# Bank2_Configuration.net
KiCad netlist of a schematic drawn in Altium Designer
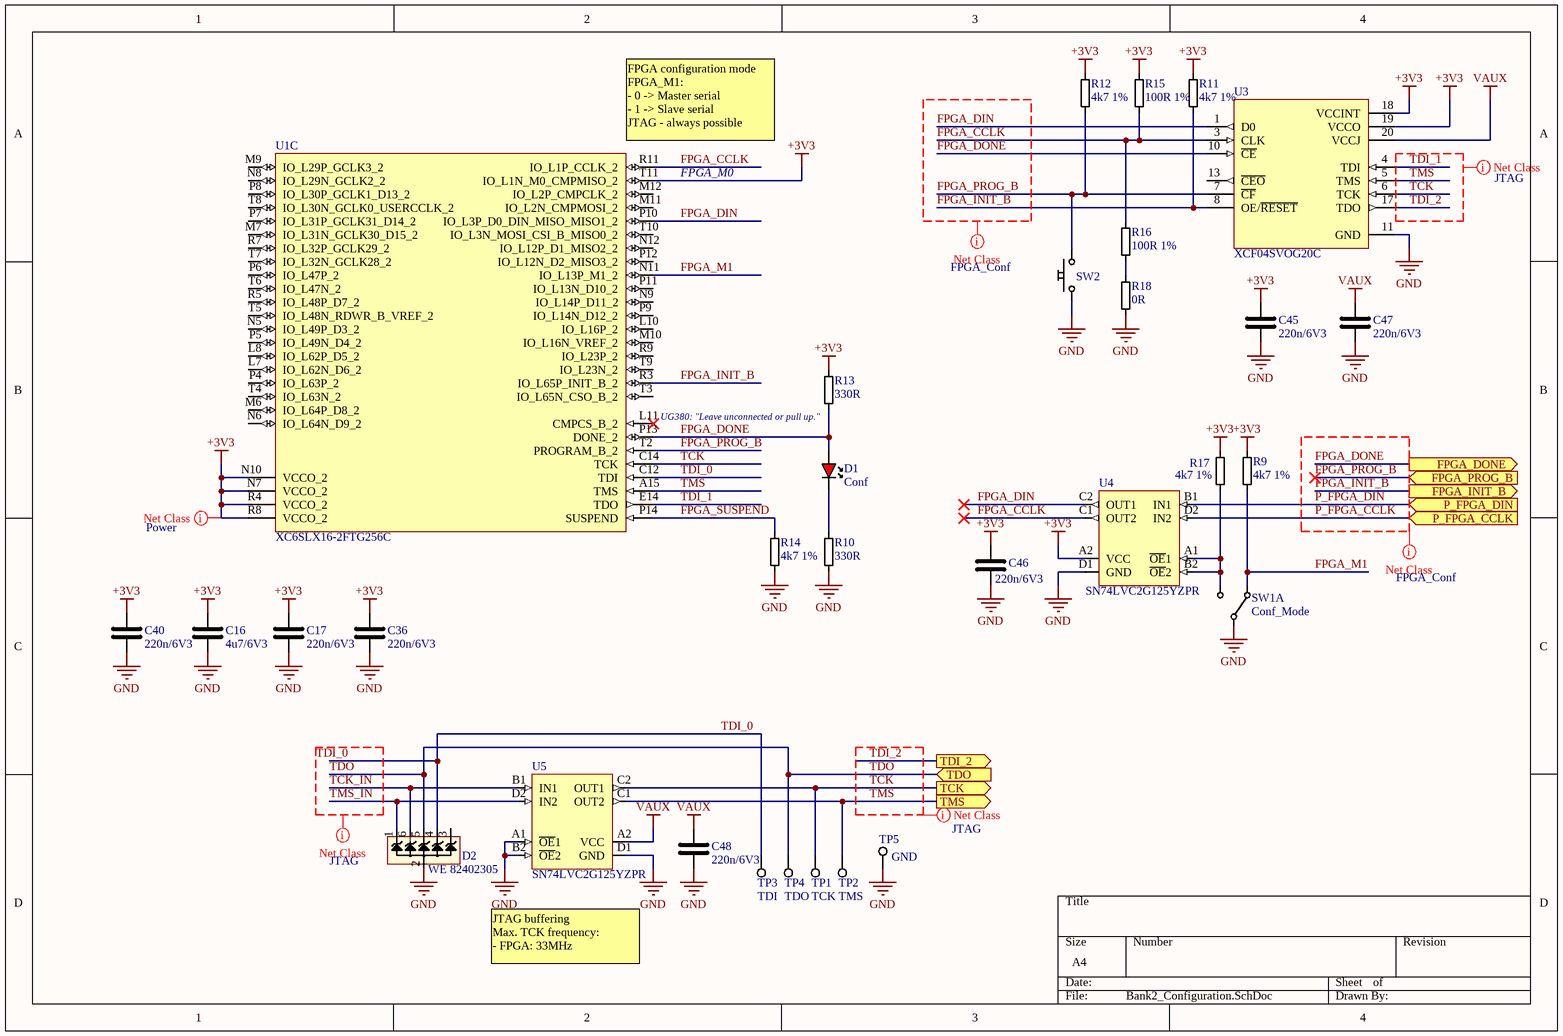
[diagram p0: Bank2_Configuration.SchDoc]

(export (version "E")
  (design (tool "Eeschema 10.0.6"))
  (components
    (comp (ref "C16") (value "4u7/6V3") (footprint "C0805_N") (libsource (lib "niceCircuits") (part "C")))
    (comp (ref "C17") (value "220n/6V3") (footprint "C0402_N") (libsource (lib "niceCircuits") (part "C")))
    (comp (ref "C36") (value "220n/6V3") (footprint "C0402_N") (libsource (lib "niceCircuits") (part "C")))
    (comp (ref "C40") (value "220n/6V3") (footprint "C0402_N") (libsource (lib "niceCircuits") (part "C")))
    (comp (ref "C45") (value "220n/6V3") (footprint "C0402_N") (libsource (lib "niceCircuits") (part "C")))
    (comp (ref "C46") (value "220n/6V3") (footprint "C0402_N") (libsource (lib "niceCircuits") (part "C")))
    (comp (ref "C47") (value "220n/6V3") (footprint "C0402_N") (libsource (lib "niceCircuits") (part "C")))
    (comp (ref "C48") (value "220n/6V3") (footprint "C0402_N") (libsource (lib "niceCircuits") (part "C")))
    (comp (ref "D1")
      (value "Conf")
      (footprint "LED0603_red_N")
      (description "Generic 0603 Super Bright Red LED")
      (libsource (lib "niceCircuits") (part "LED_0603_Red_Super_Bright"))
    )
    (comp (ref "D2")
      (value "WE 82402305")
      (footprint "SOT23-6_N")
      (description "TVS Diode WE-TVS-Standard, VRWM=5.0V")
      (libsource (lib "niceCircuits") (part "WE 82402305"))
    )
    (comp (ref "R9") (value "4k7 1%") (footprint "R0402_N") (libsource (lib "niceCircuits") (part "R")))
    (comp (ref "R10") (value "330R") (footprint "R0402_N") (libsource (lib "niceCircuits") (part "R")))
    (comp (ref "R11") (value "4k7 1%") (footprint "R0402_N") (libsource (lib "niceCircuits") (part "R")))
    (comp (ref "R12") (value "4k7 1%") (footprint "R0402_N") (libsource (lib "niceCircuits") (part "R")))
    (comp (ref "R13") (value "330R") (footprint "R0402_N") (libsource (lib "niceCircuits") (part "R")))
    (comp (ref "R14") (value "4k7 1%") (footprint "R0402_N") (libsource (lib "niceCircuits") (part "R")))
    (comp (ref "R15") (value "100R 1%") (footprint "R0402_N") (libsource (lib "niceCircuits") (part "R")))
    (comp (ref "R16") (value "100R 1%") (footprint "R0402_N") (libsource (lib "niceCircuits") (part "R")))
    (comp (ref "R17") (value "4k7 1%") (footprint "R0402_N") (libsource (lib "niceCircuits") (part "R")))
    (comp (ref "R18") (value "0R") (footprint "R0402_N") (libsource (lib "niceCircuits") (part "R")))
    (comp (ref "SW1")
      (value "Conf_Mode")
      (footprint "JS202011AQN")
      (libsource (lib "niceCircuits") (part "JS202011AQN"))
    )
    (comp (ref "SW2")
      (value "SW 4,3mm 1,5N SMD")
      (footprint "SW4,3SMD")
      (description "Microswitch 4,3mm")
      (libsource (lib "niceCircuits") (part "SW 4,3mm 1,5N SMD"))
    )
    (comp (ref "TP1") (value "TCK") (footprint "TP_20mil_SMT") (libsource (lib "niceCircuits") (part "TP")))
    (comp (ref "TP2") (value "TMS") (footprint "TP_20mil_SMT") (libsource (lib "niceCircuits") (part "TP")))
    (comp (ref "TP3") (value "TDI") (footprint "TP_20mil_SMT") (libsource (lib "niceCircuits") (part "TP")))
    (comp (ref "TP4") (value "TDO") (footprint "TP_20mil_SMT") (libsource (lib "niceCircuits") (part "TP")))
    (comp (ref "TP5") (value "GND") (footprint "TP_20mil_SMT") (libsource (lib "niceCircuits") (part "TP")))
    (comp (ref "U1")
      (value "XC6SLX16-2FTG256C")
      (footprint "Xilinx_FT256_L")
      (libsource (lib "niceCircuits") (part "XC6SLX16-2FTG256C"))
    )
    (comp (ref "U3")
      (value "XCF04SVOG20C")
      (footprint "Xilinx_TSOP20_N")
      (description "Xilinx Platform Flash configuration memory 4Mbit")
      (libsource (lib "niceCircuits") (part "XCF04SVOG20C"))
    )
    (comp (ref "U4")
      (value "SN74LVC2G125YZPR")
      (footprint "TI_YZP8")
      (libsource (lib "niceCircuits") (part "SN74LVC2G125YZPR"))
    )
    (comp (ref "U5")
      (value "SN74LVC2G125YZPR")
      (footprint "TI_YZP8")
      (libsource (lib "") (part "SN74LVC2G125YZPR_1"))
    )
  )
  (nets
    (net (code "1") (name "+3V3") (class "Default")
      (node (ref "C16") (pin "2") (pinfunction "2_2") (pintype "passive"))
      (node (ref "C17") (pin "2") (pinfunction "2_2") (pintype "passive"))
      (node (ref "C36") (pin "2") (pinfunction "2_2") (pintype "passive"))
      (node (ref "C40") (pin "2") (pinfunction "2_2") (pintype "passive"))
      (node (ref "C45") (pin "2") (pinfunction "2_2") (pintype "passive"))
      (node (ref "C46") (pin "2") (pinfunction "2_2") (pintype "passive"))
      (node (ref "R11") (pin "1") (pinfunction "1_1") (pintype "passive"))
      (node (ref "R12") (pin "1") (pinfunction "1_1") (pintype "passive"))
      (node (ref "R13") (pin "1") (pinfunction "1_1") (pintype "passive"))
      (node (ref "R15") (pin "1") (pinfunction "1_1") (pintype "passive"))
      (node (ref "R17") (pin "1") (pinfunction "1_1") (pintype "passive"))
      (node (ref "R9") (pin "1") (pinfunction "1_1") (pintype "passive"))
      (node (ref "U1") (pin "N10") (pinfunction "VCCO_2_N10") (pintype "power_in"))
      (node (ref "U1") (pin "N7") (pinfunction "VCCO_2_N7") (pintype "power_in"))
      (node (ref "U1") (pin "R4") (pinfunction "VCCO_2_R4") (pintype "power_in"))
      (node (ref "U1") (pin "R8") (pinfunction "VCCO_2_R8") (pintype "power_in"))
      (node (ref "U1") (pin "T11") (pinfunction "IO_L1N_M0_CMPMISO_2_T11") (pintype "bidirectional"))
      (node (ref "U3") (pin "18") (pinfunction "VCCINT_18") (pintype "power_in"))
      (node (ref "U3") (pin "19") (pinfunction "VCCO_19") (pintype "power_in"))
      (node (ref "U4") (pin "A2") (pinfunction "VCC_A2") (pintype "power_in"))
    )
    (net (code "2") (name "/FPGA_CCLK") (class "Default")
      (node (ref "R15") (pin "2") (pinfunction "2_2") (pintype "passive"))
      (node (ref "R16") (pin "1") (pinfunction "1_1") (pintype "passive"))
      (node (ref "U1") (pin "R11") (pinfunction "IO_L1P_CCLK_2_R11") (pintype "bidirectional"))
      (node (ref "U3") (pin "3") (pinfunction "CLK_3") (pintype "input"))
      (node (ref "U4") (pin "C1") (pinfunction "OUT2_C1") (pintype "output"))
    )
    (net (code "3") (name "/FPGA_DIN") (class "Default")
      (node (ref "U1") (pin "P10") (pinfunction "IO_L3P_D0_DIN_MISO_MISO1_2_P10") (pintype "bidirectional"))
      (node (ref "U3") (pin "1") (pinfunction "D0_1") (pintype "output"))
      (node (ref "U4") (pin "C2") (pinfunction "OUT1_C2") (pintype "output"))
    )
    (net (code "4") (name "/FPGA_DONE") (class "Default")
      (node (ref "D1") (pin "1") (pinfunction "1_1") (pintype "passive"))
      (node (ref "R13") (pin "2") (pinfunction "2_2") (pintype "passive"))
      (node (ref "U1") (pin "P13") (pinfunction "DONE_2_P13") (pintype "bidirectional"))
      (node (ref "U3") (pin "10") (pinfunction "~{CE}_10") (pintype "input"))
    )
    (net (code "5") (name "/FPGA_INIT_B") (class "Default")
      (node (ref "R11") (pin "2") (pinfunction "2_2") (pintype "passive"))
      (node (ref "U1") (pin "R3") (pinfunction "IO_L65P_INIT_B_2_R3") (pintype "bidirectional"))
      (node (ref "U3") (pin "8") (pinfunction "OE/~{RESET}_8") (pintype "open_collector"))
    )
    (net (code "6") (name "/FPGA_M1") (class "Default")
      (node (ref "R9") (pin "2") (pinfunction "2_2") (pintype "passive"))
      (node (ref "SW1") (pin "NC1") (pinfunction "NC1_NC1") (pintype "passive"))
      (node (ref "U1") (pin "N11") (pinfunction "IO_L13P_M1_2_N11") (pintype "bidirectional"))
    )
    (net (code "7") (name "/FPGA_PROG_B") (class "Default")
      (node (ref "R12") (pin "2") (pinfunction "2_2") (pintype "passive"))
      (node (ref "SW2") (pin "2") (pinfunction "2_2") (pintype "passive"))
      (node (ref "U1") (pin "T2") (pinfunction "PROGRAM_B_2_T2") (pintype "input"))
      (node (ref "U3") (pin "7") (pinfunction "~{CF}_7") (pintype "open_collector"))
    )
    (net (code "8") (name "/FPGA_SUSPEND") (class "Default")
      (node (ref "R14") (pin "1") (pinfunction "1_1") (pintype "passive"))
      (node (ref "U1") (pin "P14") (pinfunction "SUSPEND_P14") (pintype "input"))
    )
    (net (code "9") (name "/P_FPGA_CCLK") (class "Default")
      (node (ref "U4") (pin "D2") (pinfunction "IN2_D2") (pintype "input"))
    )
    (net (code "10") (name "/P_FPGA_DIN") (class "Default")
      (node (ref "U4") (pin "B1") (pinfunction "IN1_B1") (pintype "input"))
    )
    (net (code "11") (name "/TCK") (class "Default")
      (node (ref "TP1") (pin "1") (pinfunction "1_1") (pintype "passive"))
      (node (ref "U1") (pin "C14") (pinfunction "TCK_C14") (pintype "input"))
      (node (ref "U3") (pin "6") (pinfunction "TCK_6") (pintype "input"))
      (node (ref "U5") (pin "C2") (pinfunction "OUT1_C2") (pintype "output"))
    )
    (net (code "12") (name "/TCK_IN") (class "Default")
      (node (ref "D2") (pin "6") (pinfunction "C4_6") (pintype "passive"))
      (node (ref "U5") (pin "B1") (pinfunction "IN1_B1") (pintype "input"))
    )
    (net (code "13") (name "/TDI_0") (class "Default")
      (node (ref "D2") (pin "4") (pinfunction "C3_4") (pintype "passive"))
      (node (ref "TP3") (pin "1") (pinfunction "1_1") (pintype "passive"))
      (node (ref "U1") (pin "C12") (pinfunction "TDI_C12") (pintype "input"))
    )
    (net (code "14") (name "/TDI_1") (class "Default")
      (node (ref "U1") (pin "E14") (pinfunction "TDO_E14") (pintype "output"))
      (node (ref "U3") (pin "4") (pinfunction "TDI_4") (pintype "input"))
    )
    (net (code "15") (name "/TDI_2") (class "Default")
      (node (ref "U3") (pin "17") (pinfunction "TDO_17") (pintype "output"))
    )
    (net (code "16") (name "/TDO") (class "Default")
      (node (ref "D2") (pin "5") (pinfunction "A2_5") (pintype "passive"))
      (node (ref "TP4") (pin "1") (pinfunction "1_1") (pintype "passive"))
    )
    (net (code "17") (name "/TMS") (class "Default")
      (node (ref "TP2") (pin "1") (pinfunction "1_1") (pintype "passive"))
      (node (ref "U1") (pin "A15") (pinfunction "TMS_A15") (pintype "input"))
      (node (ref "U3") (pin "5") (pinfunction "TMS_5") (pintype "input"))
      (node (ref "U5") (pin "C1") (pinfunction "OUT2_C1") (pintype "output"))
    )
    (net (code "18") (name "/TMS_IN") (class "Default")
      (node (ref "D2") (pin "1") (pinfunction "C1_1") (pintype "passive"))
      (node (ref "U5") (pin "D2") (pinfunction "IN2_D2") (pintype "input"))
    )
    (net (code "19") (name "GND") (class "Default")
      (node (ref "C16") (pin "1") (pinfunction "1_1") (pintype "passive"))
      (node (ref "C17") (pin "1") (pinfunction "1_1") (pintype "passive"))
      (node (ref "C36") (pin "1") (pinfunction "1_1") (pintype "passive"))
      (node (ref "C40") (pin "1") (pinfunction "1_1") (pintype "passive"))
      (node (ref "C45") (pin "1") (pinfunction "1_1") (pintype "passive"))
      (node (ref "C46") (pin "1") (pinfunction "1_1") (pintype "passive"))
      (node (ref "C47") (pin "1") (pinfunction "1_1") (pintype "passive"))
      (node (ref "C48") (pin "1") (pinfunction "1_1") (pintype "passive"))
      (node (ref "D2") (pin "2") (pinfunction "A1_2") (pintype "passive"))
      (node (ref "R10") (pin "2") (pinfunction "2_2") (pintype "passive"))
      (node (ref "R14") (pin "2") (pinfunction "2_2") (pintype "passive"))
      (node (ref "R18") (pin "2") (pinfunction "2_2") (pintype "passive"))
      (node (ref "SW1") (pin "COM1") (pinfunction "COM1_COM1") (pintype "passive"))
      (node (ref "SW2") (pin "1") (pinfunction "1_1") (pintype "passive"))
      (node (ref "TP5") (pin "1") (pinfunction "1_1") (pintype "passive"))
      (node (ref "U3") (pin "11") (pinfunction "GND_11") (pintype "power_in"))
      (node (ref "U4") (pin "D1") (pinfunction "GND_D1") (pintype "power_in"))
      (node (ref "U5") (pin "A1") (pinfunction "~{OE}1_A1") (pintype "input"))
      (node (ref "U5") (pin "B2") (pinfunction "~{OE}2_B2") (pintype "input"))
      (node (ref "U5") (pin "D1") (pinfunction "GND_D1") (pintype "power_in"))
    )
    (net (code "20") (name "Net-(D1-Pad2)") (class "Default")
      (node (ref "D1") (pin "2") (pinfunction "2_2") (pintype "passive"))
      (node (ref "R10") (pin "1") (pinfunction "1_1") (pintype "passive"))
    )
    (net (code "21") (name "Net-(R16-Pad2)") (class "Default")
      (node (ref "R16") (pin "2") (pinfunction "2_2") (pintype "passive"))
      (node (ref "R18") (pin "1") (pinfunction "1_1") (pintype "passive"))
    )
    (net (code "22") (name "Net-(U4-~{OE}1)") (class "Default")
      (node (ref "R17") (pin "2") (pinfunction "2_2") (pintype "passive"))
      (node (ref "SW1") (pin "NO1") (pinfunction "NO1_NO1") (pintype "passive"))
      (node (ref "U4") (pin "A1") (pinfunction "~{OE}1_A1") (pintype "input"))
      (node (ref "U4") (pin "B2") (pinfunction "~{OE}2_B2") (pintype "input"))
    )
    (net (code "23") (name "VAUX") (class "Default")
      (node (ref "C47") (pin "2") (pinfunction "2_2") (pintype "passive"))
      (node (ref "C48") (pin "2") (pinfunction "2_2") (pintype "passive"))
      (node (ref "U3") (pin "20") (pinfunction "VCCJ_20") (pintype "power_in"))
      (node (ref "U5") (pin "A2") (pinfunction "VCC_A2") (pintype "power_in"))
    )
    (net (code "24") (name "unconnected-(D2-C2-Pad3)") (class "Default")
      (node (ref "D2") (pin "3") (pinfunction "C2_3") (pintype "passive"))
    )
    (net (code "25") (name "unconnected-(U1C-CMPCS_B_2-PadL11)") (class "Default")
      (node (ref "U1") (pin "L11") (pinfunction "CMPCS_B_2_L11") (pintype "input+no_connect"))
    )
    (net (code "26") (name "unconnected-(U1C-IO_L2N_CMPMOSI_2-PadM11)") (class "Default")
      (node (ref "U1") (pin "M11") (pinfunction "IO_L2N_CMPMOSI_2_M11") (pintype "bidirectional"))
    )
    (net (code "27") (name "unconnected-(U1C-IO_L2P_CMPCLK_2-PadM12)") (class "Default")
      (node (ref "U1") (pin "M12") (pinfunction "IO_L2P_CMPCLK_2_M12") (pintype "bidirectional"))
    )
    (net (code "28") (name "unconnected-(U1C-IO_L3N_MOSI_CSI_B_MISO0_2-PadT10)") (class "Default")
      (node (ref "U1") (pin "T10") (pinfunction "IO_L3N_MOSI_CSI_B_MISO0_2_T10") (pintype "bidirectional"))
    )
    (net (code "29") (name "unconnected-(U1C-IO_L12N_D2_MISO3_2-PadP12)") (class "Default")
      (node (ref "U1") (pin "P12") (pinfunction "IO_L12N_D2_MISO3_2_P12") (pintype "bidirectional"))
    )
    (net (code "30") (name "unconnected-(U1C-IO_L12P_D1_MISO2_2-PadN12)") (class "Default")
      (node (ref "U1") (pin "N12") (pinfunction "IO_L12P_D1_MISO2_2_N12") (pintype "bidirectional"))
    )
    (net (code "31") (name "unconnected-(U1C-IO_L13N_D10_2-PadP11)") (class "Default")
      (node (ref "U1") (pin "P11") (pinfunction "IO_L13N_D10_2_P11") (pintype "bidirectional"))
    )
    (net (code "32") (name "unconnected-(U1C-IO_L14N_D12_2-PadP9)") (class "Default")
      (node (ref "U1") (pin "P9") (pinfunction "IO_L14N_D12_2_P9") (pintype "bidirectional"))
    )
    (net (code "33") (name "unconnected-(U1C-IO_L14P_D11_2-PadN9)") (class "Default")
      (node (ref "U1") (pin "N9") (pinfunction "IO_L14P_D11_2_N9") (pintype "bidirectional"))
    )
    (net (code "34") (name "unconnected-(U1C-IO_L16N_VREF_2-PadM10)") (class "Default")
      (node (ref "U1") (pin "M10") (pinfunction "IO_L16N_VREF_2_M10") (pintype "bidirectional"))
    )
    (net (code "35") (name "unconnected-(U1C-IO_L16P_2-PadL10)") (class "Default")
      (node (ref "U1") (pin "L10") (pinfunction "IO_L16P_2_L10") (pintype "bidirectional"))
    )
    (net (code "36") (name "unconnected-(U1C-IO_L23N_2-PadT9)") (class "Default")
      (node (ref "U1") (pin "T9") (pinfunction "IO_L23N_2_T9") (pintype "bidirectional"))
    )
    (net (code "37") (name "unconnected-(U1C-IO_L23P_2-PadR9)") (class "Default")
      (node (ref "U1") (pin "R9") (pinfunction "IO_L23P_2_R9") (pintype "bidirectional"))
    )
    (net (code "38") (name "unconnected-(U1C-IO_L29N_GCLK2_2-PadN8)") (class "Default")
      (node (ref "U1") (pin "N8") (pinfunction "IO_L29N_GCLK2_2_N8") (pintype "bidirectional"))
    )
    (net (code "39") (name "unconnected-(U1C-IO_L29P_GCLK3_2-PadM9)") (class "Default")
      (node (ref "U1") (pin "M9") (pinfunction "IO_L29P_GCLK3_2_M9") (pintype "bidirectional"))
    )
    (net (code "40") (name "unconnected-(U1C-IO_L30N_GCLK0_USERCCLK_2-PadT8)") (class "Default")
      (node (ref "U1") (pin "T8") (pinfunction "IO_L30N_GCLK0_USERCCLK_2_T8") (pintype "bidirectional"))
    )
    (net (code "41") (name "unconnected-(U1C-IO_L30P_GCLK1_D13_2-PadP8)") (class "Default")
      (node (ref "U1") (pin "P8") (pinfunction "IO_L30P_GCLK1_D13_2_P8") (pintype "bidirectional"))
    )
    (net (code "42") (name "unconnected-(U1C-IO_L31N_GCLK30_D15_2-PadM7)") (class "Default")
      (node (ref "U1") (pin "M7") (pinfunction "IO_L31N_GCLK30_D15_2_M7") (pintype "bidirectional"))
    )
    (net (code "43") (name "unconnected-(U1C-IO_L31P_GCLK31_D14_2-PadP7)") (class "Default")
      (node (ref "U1") (pin "P7") (pinfunction "IO_L31P_GCLK31_D14_2_P7") (pintype "bidirectional"))
    )
    (net (code "44") (name "unconnected-(U1C-IO_L32N_GCLK28_2-PadT7)") (class "Default")
      (node (ref "U1") (pin "T7") (pinfunction "IO_L32N_GCLK28_2_T7") (pintype "bidirectional"))
    )
    (net (code "45") (name "unconnected-(U1C-IO_L32P_GCLK29_2-PadR7)") (class "Default")
      (node (ref "U1") (pin "R7") (pinfunction "IO_L32P_GCLK29_2_R7") (pintype "bidirectional"))
    )
    (net (code "46") (name "unconnected-(U1C-IO_L47N_2-PadT6)") (class "Default")
      (node (ref "U1") (pin "T6") (pinfunction "IO_L47N_2_T6") (pintype "bidirectional"))
    )
    (net (code "47") (name "unconnected-(U1C-IO_L47P_2-PadP6)") (class "Default")
      (node (ref "U1") (pin "P6") (pinfunction "IO_L47P_2_P6") (pintype "bidirectional"))
    )
    (net (code "48") (name "unconnected-(U1C-IO_L48N_RDWR_B_VREF_2-PadT5)") (class "Default")
      (node (ref "U1") (pin "T5") (pinfunction "IO_L48N_RDWR_B_VREF_2_T5") (pintype "bidirectional"))
    )
    (net (code "49") (name "unconnected-(U1C-IO_L48P_D7_2-PadR5)") (class "Default")
      (node (ref "U1") (pin "R5") (pinfunction "IO_L48P_D7_2_R5") (pintype "bidirectional"))
    )
    (net (code "50") (name "unconnected-(U1C-IO_L49N_D4_2-PadP5)") (class "Default")
      (node (ref "U1") (pin "P5") (pinfunction "IO_L49N_D4_2_P5") (pintype "bidirectional"))
    )
    (net (code "51") (name "unconnected-(U1C-IO_L49P_D3_2-PadN5)") (class "Default")
      (node (ref "U1") (pin "N5") (pinfunction "IO_L49P_D3_2_N5") (pintype "bidirectional"))
    )
    (net (code "52") (name "unconnected-(U1C-IO_L62N_D6_2-PadL7)") (class "Default")
      (node (ref "U1") (pin "L7") (pinfunction "IO_L62N_D6_2_L7") (pintype "bidirectional"))
    )
    (net (code "53") (name "unconnected-(U1C-IO_L62P_D5_2-PadL8)") (class "Default")
      (node (ref "U1") (pin "L8") (pinfunction "IO_L62P_D5_2_L8") (pintype "bidirectional"))
    )
    (net (code "54") (name "unconnected-(U1C-IO_L63N_2-PadT4)") (class "Default")
      (node (ref "U1") (pin "T4") (pinfunction "IO_L63N_2_T4") (pintype "bidirectional"))
    )
    (net (code "55") (name "unconnected-(U1C-IO_L63P_2-PadP4)") (class "Default")
      (node (ref "U1") (pin "P4") (pinfunction "IO_L63P_2_P4") (pintype "bidirectional"))
    )
    (net (code "56") (name "unconnected-(U1C-IO_L64N_D9_2-PadN6)") (class "Default")
      (node (ref "U1") (pin "N6") (pinfunction "IO_L64N_D9_2_N6") (pintype "bidirectional"))
    )
    (net (code "57") (name "unconnected-(U1C-IO_L64P_D8_2-PadM6)") (class "Default")
      (node (ref "U1") (pin "M6") (pinfunction "IO_L64P_D8_2_M6") (pintype "bidirectional"))
    )
    (net (code "58") (name "unconnected-(U1C-IO_L65N_CSO_B_2-PadT3)") (class "Default")
      (node (ref "U1") (pin "T3") (pinfunction "IO_L65N_CSO_B_2_T3") (pintype "bidirectional"))
    )
    (net (code "59") (name "unconnected-(U3-~{CEO}-Pad13)") (class "Default")
      (node (ref "U3") (pin "13") (pinfunction "~{CEO}_13") (pintype "output"))
    )
  )
)
